# piHatJoystick.net
KiCad netlist of a schematic drawn in EAGLE
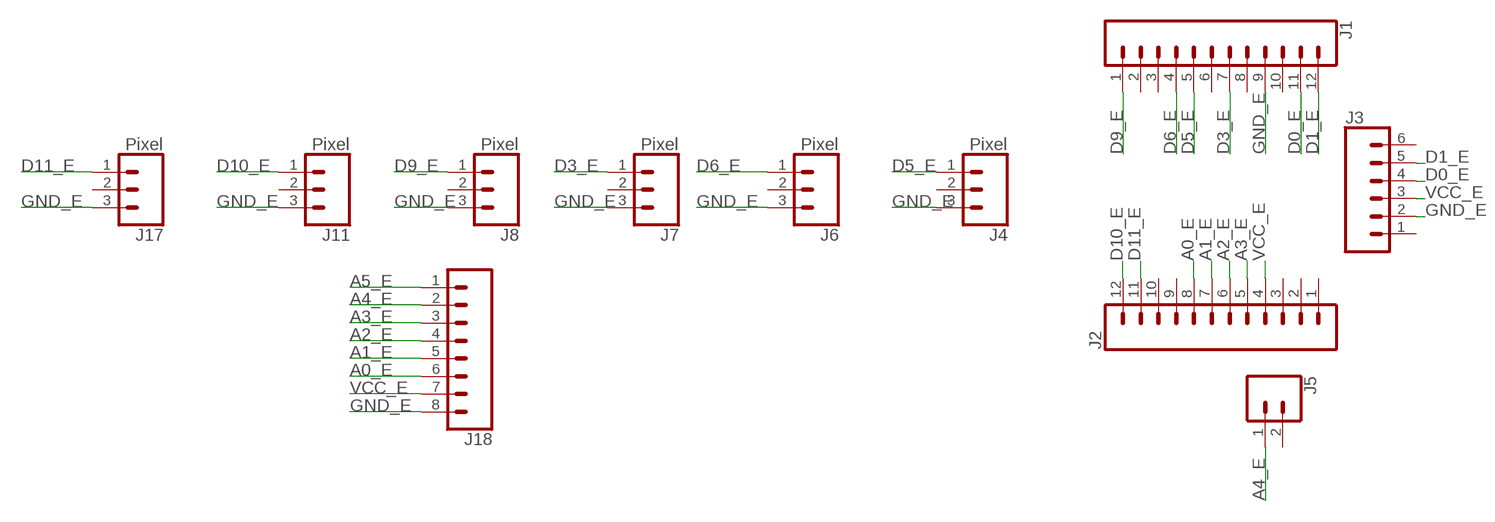
[diagram p0: schematic, sheet 1]

(export (version "E")
  (design (tool "Eeschema 10.0.6"))
  (components
    (comp (ref "J1")
      (value "CONN_12")
      (footprint "eagle-import:1X12")
      (libsource (lib "eagle-import") (part "CONN_12"))
    )
    (comp (ref "J2")
      (value "CONN_12")
      (footprint "eagle-import:1X12")
      (libsource (lib "eagle-import") (part "CONN_12"))
    )
    (comp (ref "J3")
      (value "CONN_06SILK_FEMALE_PTH")
      (footprint "eagle-import:1X06")
      (libsource (lib "eagle-import") (part "CONN_06SILK_FEMALE_PTH"))
    )
    (comp (ref "J4")
      (value "Pixel")
      (footprint "eagle-import:1X03")
      (libsource (lib "eagle-import") (part "CONN_03"))
    )
    (comp (ref "J5")
      (value "CONN_02")
      (footprint "eagle-import:1X02")
      (libsource (lib "eagle-import") (part "CONN_02"))
    )
    (comp (ref "J6")
      (value "Pixel")
      (footprint "eagle-import:1X03")
      (libsource (lib "eagle-import") (part "CONN_03"))
    )
    (comp (ref "J7")
      (value "Pixel")
      (footprint "eagle-import:1X03")
      (libsource (lib "eagle-import") (part "CONN_03"))
    )
    (comp (ref "J8")
      (value "Pixel")
      (footprint "eagle-import:1X03")
      (libsource (lib "eagle-import") (part "CONN_03"))
    )
    (comp (ref "J11")
      (value "Pixel")
      (footprint "eagle-import:1X03")
      (libsource (lib "eagle-import") (part "CONN_03"))
    )
    (comp (ref "J17")
      (value "Pixel")
      (footprint "eagle-import:1X03")
      (libsource (lib "eagle-import") (part "CONN_03"))
    )
    (comp (ref "J18")
      (value "CONN_08\"")
      (footprint "eagle-import:1X08")
      (libsource (lib "eagle-import") (part "CONN_08{dblquote}"))
    )
  )
  (nets
    (net (code "1") (name "/A0_E") (class "Default")
      (node (ref "J18") (pin "6") (pinfunction "6_6") (pintype "passive"))
      (node (ref "J2") (pin "8") (pinfunction "8_8") (pintype "passive"))
    )
    (net (code "2") (name "/A1_E") (class "Default")
      (node (ref "J18") (pin "5") (pinfunction "5_5") (pintype "passive"))
      (node (ref "J2") (pin "7") (pinfunction "7_7") (pintype "passive"))
    )
    (net (code "3") (name "/A2_E") (class "Default")
      (node (ref "J18") (pin "4") (pinfunction "4_4") (pintype "passive"))
      (node (ref "J2") (pin "6") (pinfunction "6_6") (pintype "passive"))
    )
    (net (code "4") (name "/A3_E") (class "Default")
      (node (ref "J18") (pin "3") (pinfunction "3_3") (pintype "passive"))
      (node (ref "J2") (pin "5") (pinfunction "5_5") (pintype "passive"))
    )
    (net (code "5") (name "/A4_E") (class "Default")
      (node (ref "J18") (pin "2") (pinfunction "2_2") (pintype "passive"))
      (node (ref "J5") (pin "1") (pinfunction "1_1") (pintype "passive"))
    )
    (net (code "6") (name "/A5_E") (class "Default")
      (node (ref "J18") (pin "1") (pinfunction "1_1") (pintype "passive"))
    )
    (net (code "7") (name "/D0_E") (class "Default")
      (node (ref "J1") (pin "11") (pinfunction "11_11") (pintype "passive"))
      (node (ref "J3") (pin "4") (pinfunction "4_4") (pintype "passive"))
    )
    (net (code "8") (name "/D1_E") (class "Default")
      (node (ref "J1") (pin "12") (pinfunction "12_12") (pintype "passive"))
      (node (ref "J3") (pin "5") (pinfunction "5_5") (pintype "passive"))
    )
    (net (code "9") (name "/D3_E") (class "Default")
      (node (ref "J1") (pin "7") (pinfunction "7_7") (pintype "passive"))
      (node (ref "J7") (pin "1") (pinfunction "1_1") (pintype "passive"))
    )
    (net (code "10") (name "/D5_E") (class "Default")
      (node (ref "J1") (pin "5") (pinfunction "5_5") (pintype "passive"))
      (node (ref "J4") (pin "1") (pinfunction "1_1") (pintype "passive"))
    )
    (net (code "11") (name "/D6_E") (class "Default")
      (node (ref "J1") (pin "4") (pinfunction "4_4") (pintype "passive"))
      (node (ref "J6") (pin "1") (pinfunction "1_1") (pintype "passive"))
    )
    (net (code "12") (name "/D9_E") (class "Default")
      (node (ref "J1") (pin "1") (pinfunction "1_1") (pintype "passive"))
      (node (ref "J8") (pin "1") (pinfunction "1_1") (pintype "passive"))
    )
    (net (code "13") (name "/D10_E") (class "Default")
      (node (ref "J11") (pin "1") (pinfunction "1_1") (pintype "passive"))
      (node (ref "J2") (pin "12") (pinfunction "12_12") (pintype "passive"))
    )
    (net (code "14") (name "/D11_E") (class "Default")
      (node (ref "J17") (pin "1") (pinfunction "1_1") (pintype "passive"))
      (node (ref "J2") (pin "11") (pinfunction "11_11") (pintype "passive"))
    )
    (net (code "15") (name "/GND_E") (class "Default")
      (node (ref "J1") (pin "9") (pinfunction "9_9") (pintype "passive"))
      (node (ref "J11") (pin "3") (pinfunction "3_3") (pintype "passive"))
      (node (ref "J17") (pin "3") (pinfunction "3_3") (pintype "passive"))
      (node (ref "J18") (pin "8") (pinfunction "8_8") (pintype "passive"))
      (node (ref "J3") (pin "2") (pinfunction "2_2") (pintype "passive"))
      (node (ref "J4") (pin "3") (pinfunction "3_3") (pintype "passive"))
      (node (ref "J6") (pin "3") (pinfunction "3_3") (pintype "passive"))
      (node (ref "J7") (pin "3") (pinfunction "3_3") (pintype "passive"))
      (node (ref "J8") (pin "3") (pinfunction "3_3") (pintype "passive"))
    )
    (net (code "16") (name "/VCC_E") (class "Default")
      (node (ref "J18") (pin "7") (pinfunction "7_7") (pintype "passive"))
      (node (ref "J2") (pin "4") (pinfunction "4_4") (pintype "passive"))
      (node (ref "J3") (pin "3") (pinfunction "3_3") (pintype "passive"))
    )
    (net (code "17") (name "unconnected-(J1-Pad2)") (class "Default")
      (node (ref "J1") (pin "2") (pinfunction "2_2") (pintype "passive"))
    )
    (net (code "18") (name "unconnected-(J1-Pad3)") (class "Default")
      (node (ref "J1") (pin "3") (pinfunction "3_3") (pintype "passive"))
    )
    (net (code "19") (name "unconnected-(J1-Pad6)") (class "Default")
      (node (ref "J1") (pin "6") (pinfunction "6_6") (pintype "passive"))
    )
    (net (code "20") (name "unconnected-(J1-Pad8)") (class "Default")
      (node (ref "J1") (pin "8") (pinfunction "8_8") (pintype "passive"))
    )
    (net (code "21") (name "unconnected-(J1-Pad10)") (class "Default")
      (node (ref "J1") (pin "10") (pinfunction "10_10") (pintype "passive"))
    )
    (net (code "22") (name "unconnected-(J2-Pad1)") (class "Default")
      (node (ref "J2") (pin "1") (pinfunction "1_1") (pintype "passive"))
    )
    (net (code "23") (name "unconnected-(J2-Pad2)") (class "Default")
      (node (ref "J2") (pin "2") (pinfunction "2_2") (pintype "passive"))
    )
    (net (code "24") (name "unconnected-(J2-Pad3)") (class "Default")
      (node (ref "J2") (pin "3") (pinfunction "3_3") (pintype "passive"))
    )
    (net (code "25") (name "unconnected-(J2-Pad9)") (class "Default")
      (node (ref "J2") (pin "9") (pinfunction "9_9") (pintype "passive"))
    )
    (net (code "26") (name "unconnected-(J2-Pad10)") (class "Default")
      (node (ref "J2") (pin "10") (pinfunction "10_10") (pintype "passive"))
    )
    (net (code "27") (name "unconnected-(J3-Pad1)") (class "Default")
      (node (ref "J3") (pin "1") (pinfunction "1_1") (pintype "passive"))
    )
    (net (code "28") (name "unconnected-(J3-Pad6)") (class "Default")
      (node (ref "J3") (pin "6") (pinfunction "6_6") (pintype "passive"))
    )
    (net (code "29") (name "unconnected-(J4-Pad2)") (class "Default")
      (node (ref "J4") (pin "2") (pinfunction "2_2") (pintype "passive"))
    )
    (net (code "30") (name "unconnected-(J5-Pad2)") (class "Default")
      (node (ref "J5") (pin "2") (pinfunction "2_2") (pintype "passive"))
    )
    (net (code "31") (name "unconnected-(J6-Pad2)") (class "Default")
      (node (ref "J6") (pin "2") (pinfunction "2_2") (pintype "passive"))
    )
    (net (code "32") (name "unconnected-(J7-Pad2)") (class "Default")
      (node (ref "J7") (pin "2") (pinfunction "2_2") (pintype "passive"))
    )
    (net (code "33") (name "unconnected-(J8-Pad2)") (class "Default")
      (node (ref "J8") (pin "2") (pinfunction "2_2") (pintype "passive"))
    )
    (net (code "34") (name "unconnected-(J11-Pad2)") (class "Default")
      (node (ref "J11") (pin "2") (pinfunction "2_2") (pintype "passive"))
    )
    (net (code "35") (name "unconnected-(J17-Pad2)") (class "Default")
      (node (ref "J17") (pin "2") (pinfunction "2_2") (pintype "passive"))
    )
  )
)
